# Power.net
KiCad netlist of a schematic drawn in Altium Designer
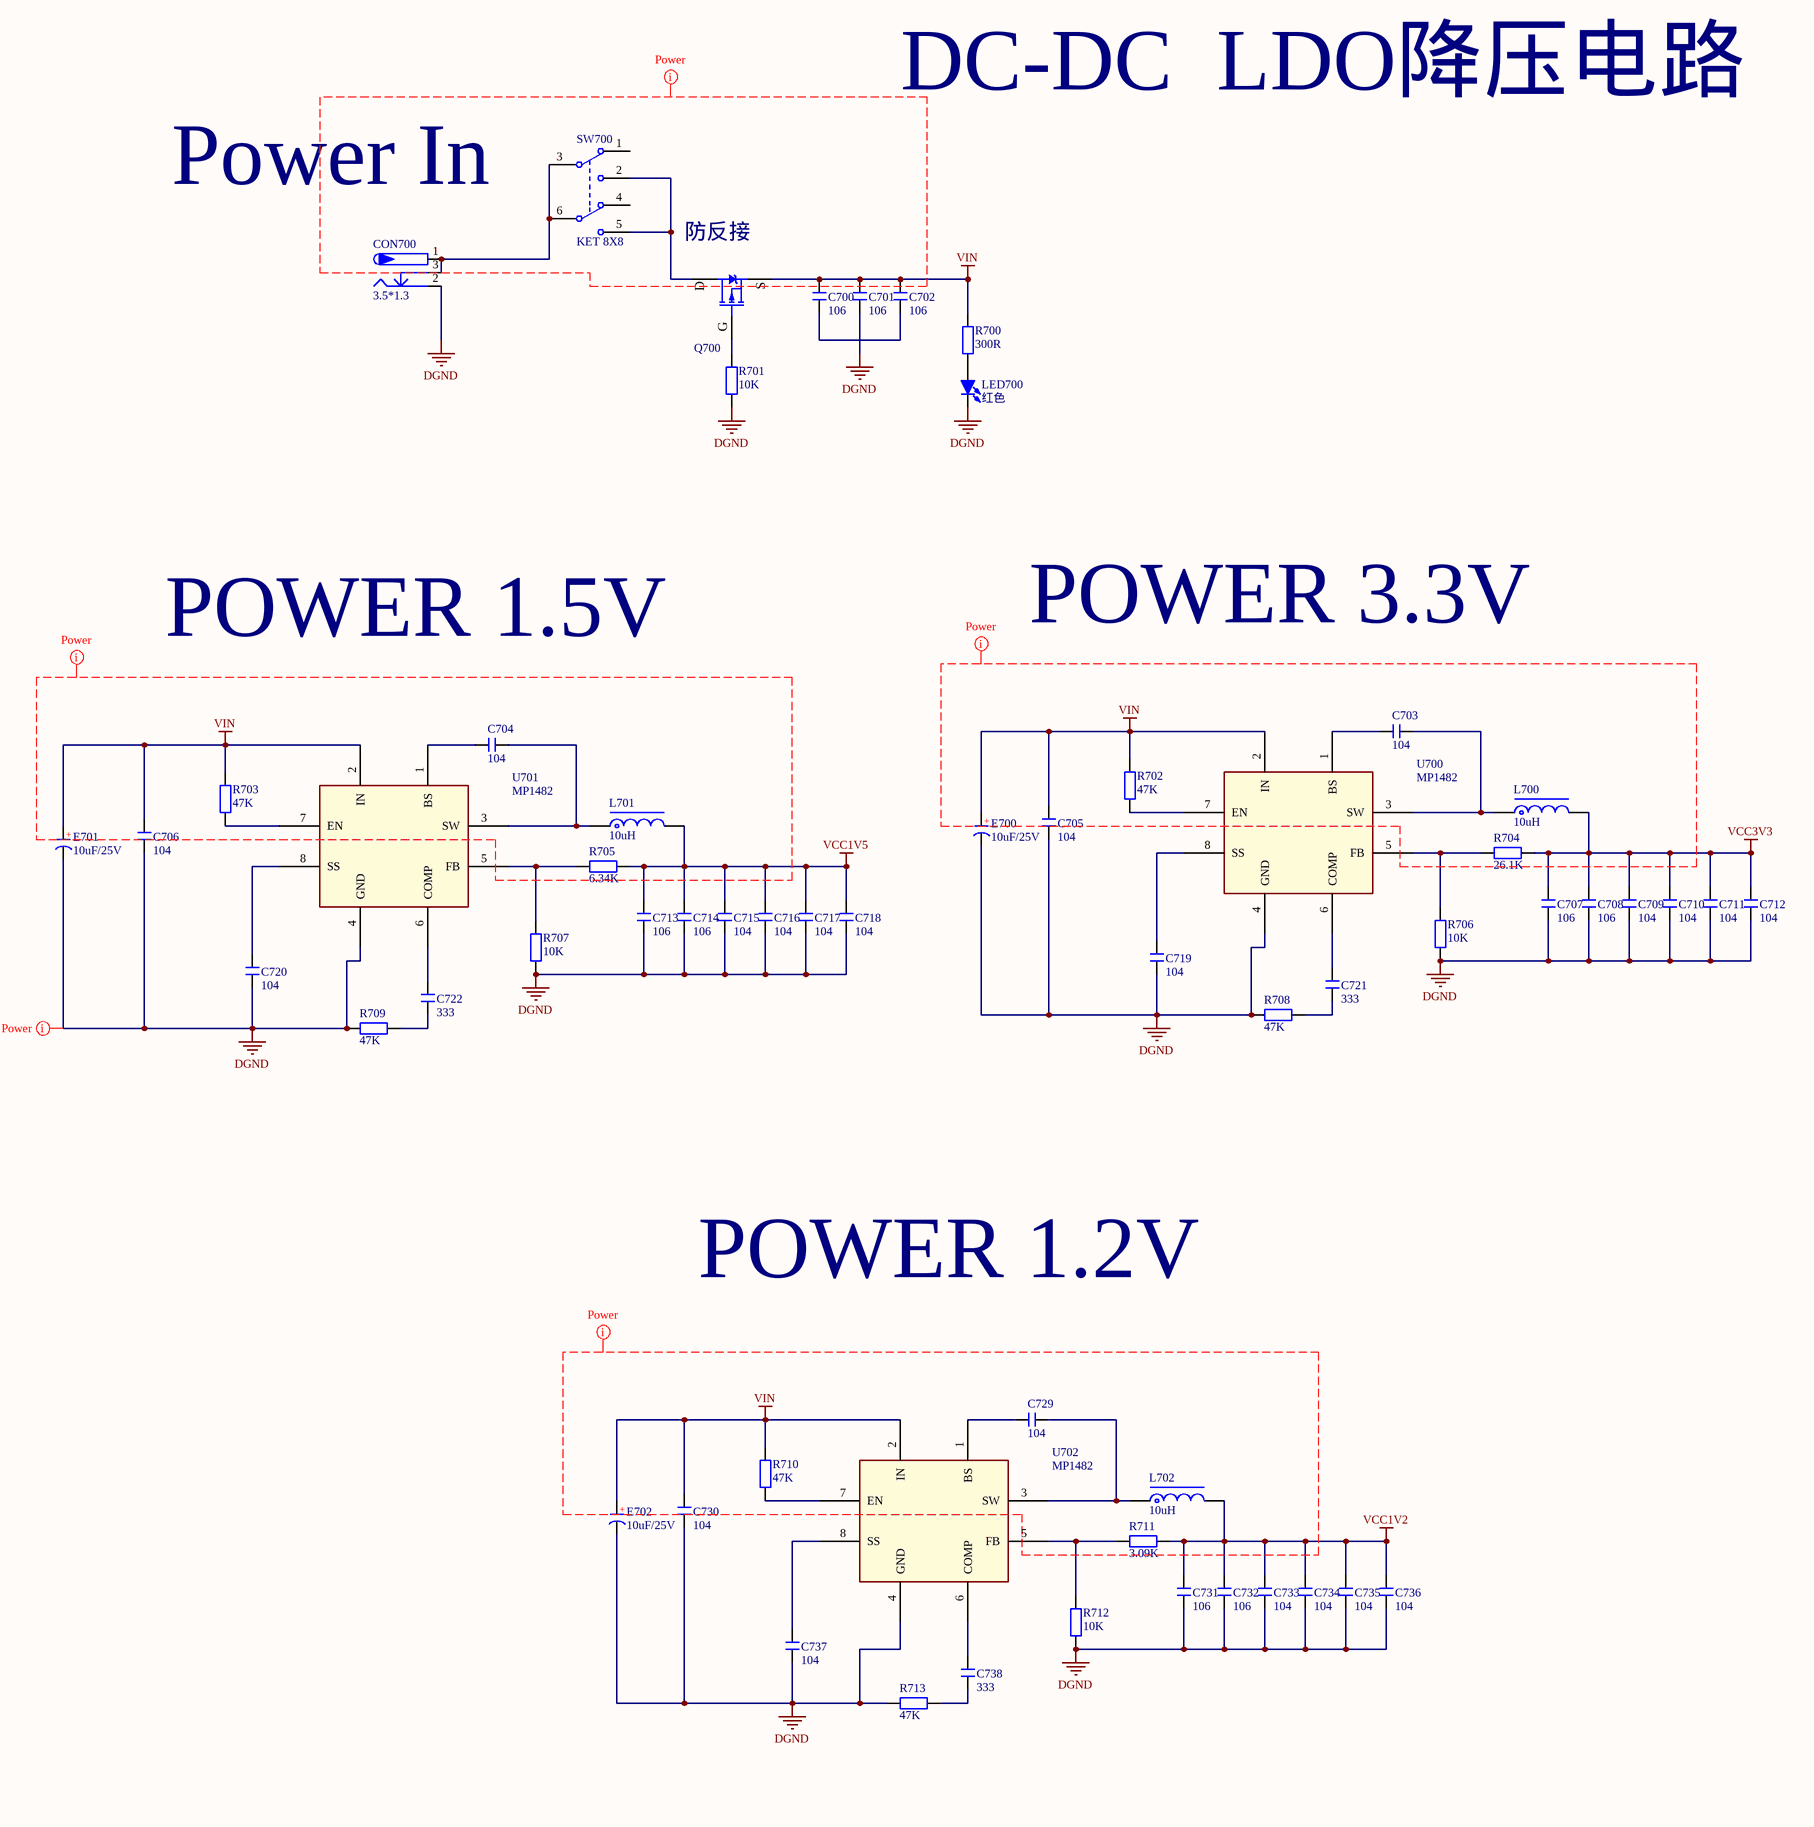
[diagram p0: Power.SchDoc, left]
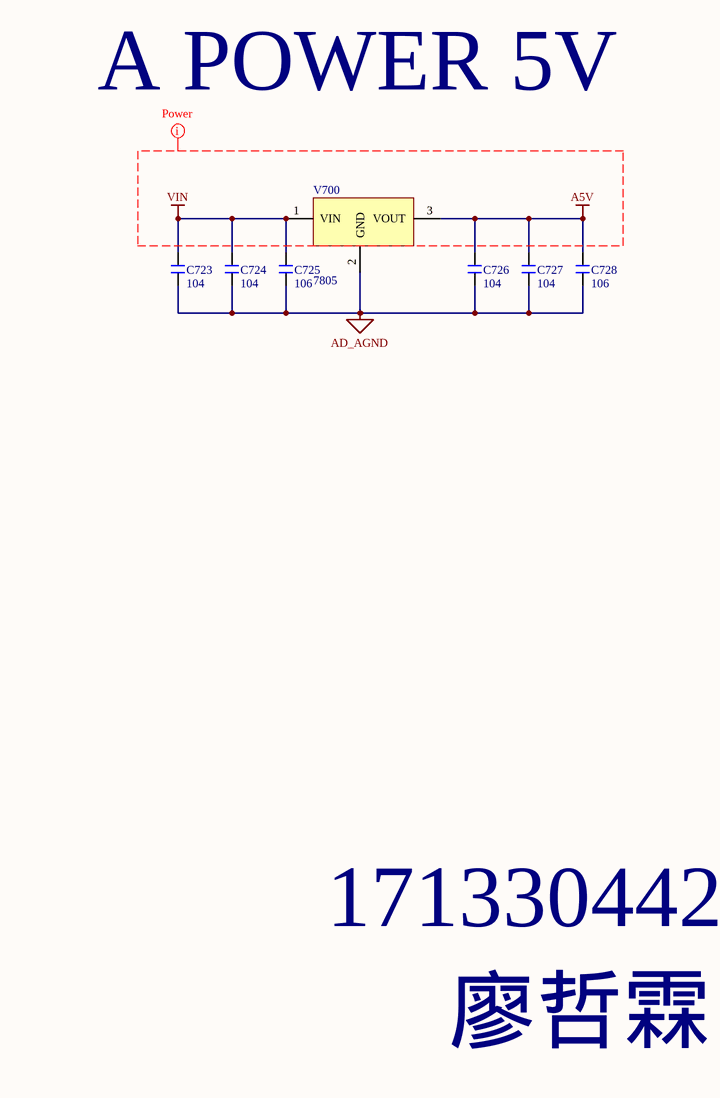
[diagram p1: Power.SchDoc, right]

(export (version "E")
  (design (tool "Eeschema 10.0.6"))
  (components
    (comp (ref "C700")
      (value "106")
      (footprint "C 0402_M")
      (description "无极性贴片电容")
      (fields (field (name "版权归属") "源创客"))
      (libsource (lib "3.1   - 电阻-电容-电感") (part "C"))
    )
    (comp (ref "C701")
      (value "106")
      (footprint "C 0402_M")
      (description "无极性贴片电容")
      (fields (field (name "版权归属") "源创客"))
      (libsource (lib "3.1   - 电阻-电容-电感") (part "C"))
    )
    (comp (ref "C702")
      (value "106")
      (footprint "C 0402_M")
      (description "无极性贴片电容")
      (fields (field (name "版权归属") "源创客"))
      (libsource (lib "3.1   - 电阻-电容-电感") (part "C"))
    )
    (comp (ref "C703")
      (value "104")
      (footprint "C 0402_M")
      (description "无极性贴片电容")
      (fields (field (name "版权归属") "源创客"))
      (libsource (lib "3.1   - 电阻-电容-电感") (part "C"))
    )
    (comp (ref "C704")
      (value "104")
      (footprint "C 0402_M")
      (description "无极性贴片电容")
      (fields (field (name "版权归属") "源创客"))
      (libsource (lib "3.1   - 电阻-电容-电感") (part "C"))
    )
    (comp (ref "C705")
      (value "104")
      (footprint "C 0402_M")
      (description "无极性贴片电容")
      (fields (field (name "版权归属") "源创客"))
      (libsource (lib "3.1   - 电阻-电容-电感") (part "C"))
    )
    (comp (ref "C706")
      (value "104")
      (footprint "C 0402_M")
      (description "无极性贴片电容")
      (fields (field (name "版权归属") "源创客"))
      (libsource (lib "3.1   - 电阻-电容-电感") (part "C"))
    )
    (comp (ref "C707")
      (value "106")
      (footprint "C 0402_M")
      (description "无极性贴片电容")
      (fields (field (name "版权归属") "源创客"))
      (libsource (lib "3.1   - 电阻-电容-电感") (part "C"))
    )
    (comp (ref "C708")
      (value "106")
      (footprint "C 0402_M")
      (description "无极性贴片电容")
      (fields (field (name "版权归属") "源创客"))
      (libsource (lib "3.1   - 电阻-电容-电感") (part "C"))
    )
    (comp (ref "C709")
      (value "104")
      (footprint "C 0402_M")
      (description "无极性贴片电容")
      (fields (field (name "版权归属") "源创客"))
      (libsource (lib "3.1   - 电阻-电容-电感") (part "C"))
    )
    (comp (ref "C710")
      (value "104")
      (footprint "C 0402_M")
      (description "无极性贴片电容")
      (fields (field (name "版权归属") "源创客"))
      (libsource (lib "3.1   - 电阻-电容-电感") (part "C"))
    )
    (comp (ref "C711")
      (value "104")
      (footprint "C 0402_M")
      (description "无极性贴片电容")
      (fields (field (name "版权归属") "源创客"))
      (libsource (lib "3.1   - 电阻-电容-电感") (part "C"))
    )
    (comp (ref "C712")
      (value "104")
      (footprint "C 0402_M")
      (description "无极性贴片电容")
      (fields (field (name "版权归属") "源创客"))
      (libsource (lib "3.1   - 电阻-电容-电感") (part "C"))
    )
    (comp (ref "C713")
      (value "106")
      (footprint "C 0402_M")
      (description "无极性贴片电容")
      (fields (field (name "版权归属") "源创客"))
      (libsource (lib "3.1   - 电阻-电容-电感") (part "C"))
    )
    (comp (ref "C714")
      (value "106")
      (footprint "C 0402_M")
      (description "无极性贴片电容")
      (fields (field (name "版权归属") "源创客"))
      (libsource (lib "3.1   - 电阻-电容-电感") (part "C"))
    )
    (comp (ref "C715")
      (value "104")
      (footprint "C 0402_M")
      (description "无极性贴片电容")
      (fields (field (name "版权归属") "源创客"))
      (libsource (lib "3.1   - 电阻-电容-电感") (part "C"))
    )
    (comp (ref "C716")
      (value "104")
      (footprint "C 0402_M")
      (description "无极性贴片电容")
      (fields (field (name "版权归属") "源创客"))
      (libsource (lib "3.1   - 电阻-电容-电感") (part "C"))
    )
    (comp (ref "C717")
      (value "104")
      (footprint "C 0402_M")
      (description "无极性贴片电容")
      (fields (field (name "版权归属") "源创客"))
      (libsource (lib "3.1   - 电阻-电容-电感") (part "C"))
    )
    (comp (ref "C718")
      (value "104")
      (footprint "C 0402_M")
      (description "无极性贴片电容")
      (fields (field (name "版权归属") "源创客"))
      (libsource (lib "3.1   - 电阻-电容-电感") (part "C"))
    )
    (comp (ref "C719")
      (value "104")
      (footprint "C 0402_M")
      (description "无极性贴片电容")
      (fields (field (name "版权归属") "源创客"))
      (libsource (lib "3.1   - 电阻-电容-电感") (part "C"))
    )
    (comp (ref "C720")
      (value "104")
      (footprint "C 0402_M")
      (description "无极性贴片电容")
      (fields (field (name "版权归属") "源创客"))
      (libsource (lib "3.1   - 电阻-电容-电感") (part "C"))
    )
    (comp (ref "C721")
      (value "333")
      (footprint "C 0402_M")
      (description "无极性贴片电容")
      (fields (field (name "版权归属") "源创客"))
      (libsource (lib "3.1   - 电阻-电容-电感") (part "C"))
    )
    (comp (ref "C722")
      (value "333")
      (footprint "C 0402_M")
      (description "无极性贴片电容")
      (fields (field (name "版权归属") "源创客"))
      (libsource (lib "3.1   - 电阻-电容-电感") (part "C"))
    )
    (comp (ref "C723")
      (value "104")
      (footprint "C 0402_M")
      (description "无极性贴片电容")
      (fields (field (name "版权归属") "源创客"))
      (libsource (lib "3.1   - 电阻-电容-电感") (part "C"))
    )
    (comp (ref "C724")
      (value "104")
      (footprint "C 0402_M")
      (description "无极性贴片电容")
      (fields (field (name "版权归属") "源创客"))
      (libsource (lib "3.1   - 电阻-电容-电感") (part "C"))
    )
    (comp (ref "C725")
      (value "106")
      (footprint "C 0402_M")
      (description "无极性贴片电容")
      (fields (field (name "版权归属") "源创客"))
      (libsource (lib "3.1   - 电阻-电容-电感") (part "C"))
    )
    (comp (ref "C726")
      (value "104")
      (footprint "C 0402_M")
      (description "无极性贴片电容")
      (fields (field (name "版权归属") "源创客"))
      (libsource (lib "3.1   - 电阻-电容-电感") (part "C"))
    )
    (comp (ref "C727")
      (value "104")
      (footprint "C 0402_M")
      (description "无极性贴片电容")
      (fields (field (name "版权归属") "源创客"))
      (libsource (lib "3.1   - 电阻-电容-电感") (part "C"))
    )
    (comp (ref "C728")
      (value "106")
      (footprint "C 0402_M")
      (description "无极性贴片电容")
      (fields (field (name "版权归属") "源创客"))
      (libsource (lib "3.1   - 电阻-电容-电感") (part "C"))
    )
    (comp (ref "C729")
      (value "104")
      (footprint "C 0402_M")
      (description "无极性贴片电容")
      (fields (field (name "版权归属") "源创客"))
      (libsource (lib "3.1   - 电阻-电容-电感") (part "C"))
    )
    (comp (ref "C730")
      (value "104")
      (footprint "C 0402_M")
      (description "无极性贴片电容")
      (fields (field (name "版权归属") "源创客"))
      (libsource (lib "3.1   - 电阻-电容-电感") (part "C"))
    )
    (comp (ref "C731")
      (value "106")
      (footprint "C 0402_M")
      (description "无极性贴片电容")
      (fields (field (name "版权归属") "源创客"))
      (libsource (lib "3.1   - 电阻-电容-电感") (part "C"))
    )
    (comp (ref "C732")
      (value "106")
      (footprint "C 0402_M")
      (description "无极性贴片电容")
      (fields (field (name "版权归属") "源创客"))
      (libsource (lib "3.1   - 电阻-电容-电感") (part "C"))
    )
    (comp (ref "C733")
      (value "104")
      (footprint "C 0402_M")
      (description "无极性贴片电容")
      (fields (field (name "版权归属") "源创客"))
      (libsource (lib "3.1   - 电阻-电容-电感") (part "C"))
    )
    (comp (ref "C734")
      (value "104")
      (footprint "C 0402_M")
      (description "无极性贴片电容")
      (fields (field (name "版权归属") "源创客"))
      (libsource (lib "3.1   - 电阻-电容-电感") (part "C"))
    )
    (comp (ref "C735")
      (value "104")
      (footprint "C 0402_M")
      (description "无极性贴片电容")
      (fields (field (name "版权归属") "源创客"))
      (libsource (lib "3.1   - 电阻-电容-电感") (part "C"))
    )
    (comp (ref "C736")
      (value "104")
      (footprint "C 0402_M")
      (description "无极性贴片电容")
      (fields (field (name "版权归属") "源创客"))
      (libsource (lib "3.1   - 电阻-电容-电感") (part "C"))
    )
    (comp (ref "C737")
      (value "104")
      (footprint "C 0402_M")
      (description "无极性贴片电容")
      (fields (field (name "版权归属") "源创客"))
      (libsource (lib "3.1   - 电阻-电容-电感") (part "C"))
    )
    (comp (ref "C738")
      (value "333")
      (footprint "C 0402_M")
      (description "无极性贴片电容")
      (fields (field (name "版权归属") "源创客"))
      (libsource (lib "3.1   - 电阻-电容-电感") (part "C"))
    )
    (comp (ref "CON700")
      (value "3.5*1.3")
      (footprint "DC-005")
      (description "低压电源接口")
      (fields (field (name "版权归属") "源创客"))
      (libsource (lib "4.1   - 接口类") (part "P-DC"))
    )
    (comp (ref "E700")
      (value "10uF/25V")
      (footprint "CS 2.5*6.3*11 - C")
      (description "直插固态电容")
      (fields (field (name "版权归属") "源创客"))
      (libsource (lib "3.1   - 电阻-电容-电感") (part "C-CS"))
    )
    (comp (ref "E701")
      (value "10uF/25V")
      (footprint "CS 2.5*6.3*11 - C")
      (description "直插固态电容")
      (fields (field (name "版权归属") "源创客"))
      (libsource (lib "3.1   - 电阻-电容-电感") (part "C-CS"))
    )
    (comp (ref "E702")
      (value "10uF/25V")
      (footprint "CS 2.5*6.3*11 - C")
      (description "直插固态电容")
      (fields (field (name "版权归属") "源创客"))
      (libsource (lib "3.1   - 电阻-电容-电感") (part "C-CS"))
    )
    (comp (ref "L700")
      (value "10uH")
      (footprint "CD43")
      (description "贴片功率电感")
      (fields (field (name "版权归属") "源创客"))
      (libsource (lib "3.1   - 电阻-电容-电感") (part "L-CD"))
    )
    (comp (ref "L701")
      (value "10uH")
      (footprint "CD43")
      (description "贴片功率电感")
      (fields (field (name "版权归属") "源创客"))
      (libsource (lib "3.1   - 电阻-电容-电感") (part "L-CD"))
    )
    (comp (ref "L702")
      (value "10uH")
      (footprint "CD43")
      (description "贴片功率电感")
      (fields (field (name "版权归属") "源创客"))
      (libsource (lib "3.1   - 电阻-电容-电感") (part "L-CD"))
    )
    (comp (ref "LED700")
      (value "红色")
      (footprint "LED 0603W")
      (description "贴片LED")
      (fields (field (name "版权归属") "源创客"))
      (libsource (lib "9.1   - LED") (part "LED-SMD"))
    )
    (comp (ref "Q700")
      (value "D15P05")
      (footprint "TO252")
      (description "P沟道场效应管")
      (fields (field (name "版权归属") "源创客"))
      (libsource (lib "6.1   - 场效应管-可控硅") (part "D15P05"))
    )
    (comp (ref "R700")
      (value "300R")
      (footprint "R 0402_M")
      (description "贴片电阻")
      (fields (field (name "版权归属") "源创客"))
      (libsource (lib "3.1   - 电阻-电容-电感") (part "R"))
    )
    (comp (ref "R701")
      (value "10K")
      (footprint "R 0402_M")
      (description "贴片电阻")
      (fields (field (name "版权归属") "源创客"))
      (libsource (lib "3.1   - 电阻-电容-电感") (part "R"))
    )
    (comp (ref "R702")
      (value "47K")
      (footprint "R 0402_M")
      (description "贴片电阻")
      (fields (field (name "版权归属") "源创客"))
      (libsource (lib "3.1   - 电阻-电容-电感") (part "R"))
    )
    (comp (ref "R703")
      (value "47K")
      (footprint "R 0402_M")
      (description "贴片电阻")
      (fields (field (name "版权归属") "源创客"))
      (libsource (lib "3.1   - 电阻-电容-电感") (part "R"))
    )
    (comp (ref "R704")
      (value "26.1K")
      (footprint "R 0402_M")
      (description "贴片电阻")
      (fields (field (name "版权归属") "源创客"))
      (libsource (lib "3.1   - 电阻-电容-电感") (part "R"))
    )
    (comp (ref "R705")
      (value "6.34K")
      (footprint "R 0402_M")
      (description "贴片电阻")
      (fields (field (name "版权归属") "源创客"))
      (libsource (lib "3.1   - 电阻-电容-电感") (part "R"))
    )
    (comp (ref "R706")
      (value "10K")
      (footprint "R 0402_M")
      (description "贴片电阻")
      (fields (field (name "版权归属") "源创客"))
      (libsource (lib "3.1   - 电阻-电容-电感") (part "R"))
    )
    (comp (ref "R707")
      (value "10K")
      (footprint "R 0402_M")
      (description "贴片电阻")
      (fields (field (name "版权归属") "源创客"))
      (libsource (lib "3.1   - 电阻-电容-电感") (part "R"))
    )
    (comp (ref "R708")
      (value "47K")
      (footprint "R 0402_M")
      (description "贴片电阻")
      (fields (field (name "版权归属") "源创客"))
      (libsource (lib "3.1   - 电阻-电容-电感") (part "R"))
    )
    (comp (ref "R709")
      (value "47K")
      (footprint "R 0402_M")
      (description "贴片电阻")
      (fields (field (name "版权归属") "源创客"))
      (libsource (lib "3.1   - 电阻-电容-电感") (part "R"))
    )
    (comp (ref "R710")
      (value "47K")
      (footprint "R 0402_M")
      (description "贴片电阻")
      (fields (field (name "版权归属") "源创客"))
      (libsource (lib "3.1   - 电阻-电容-电感") (part "R"))
    )
    (comp (ref "R711")
      (value "3.09K")
      (footprint "R 0402_M")
      (description "贴片电阻")
      (fields (field (name "版权归属") "源创客"))
      (libsource (lib "3.1   - 电阻-电容-电感") (part "R"))
    )
    (comp (ref "R712")
      (value "10K")
      (footprint "R 0402_M")
      (description "贴片电阻")
      (fields (field (name "版权归属") "源创客"))
      (libsource (lib "3.1   - 电阻-电容-电感") (part "R"))
    )
    (comp (ref "R713")
      (value "47K")
      (footprint "R 0402_M")
      (description "贴片电阻")
      (fields (field (name "版权归属") "源创客"))
      (libsource (lib "3.1   - 电阻-电容-电感") (part "R"))
    )
    (comp (ref "SW700")
      (value "KET 8X8")
      (footprint "KFT DIP-8X8")
      (description "8*8自锁开关")
      (fields (field (name "版权归属") "源创客"))
      (libsource (lib "5.1   - 按键-开关") (part "KET 8X8"))
    )
    (comp (ref "U700")
      (value "MP1482")
      (footprint "SOP8_M")
      (libsource (lib "altium-import") (part "root_0_MP1482_"))
    )
    (comp (ref "U701")
      (value "MP1482")
      (footprint "SOP8_M")
      (libsource (lib "altium-import") (part "root_0_MP1482_"))
    )
    (comp (ref "U702")
      (value "MP1482")
      (footprint "SOP8_M")
      (libsource (lib "altium-import") (part "root_0_MP1482_"))
    )
    (comp (ref "V700")
      (value "7805")
      (footprint "TO252")
      (description "线性稳压芯片")
      (fields (field (name "版权归属") "源创客"))
      (libsource (lib "1.3   - 电源类芯片") (part "78xx"))
    )
  )
  (nets
    (net (code "1") (name "A5V") (class "Default")
      (node (ref "C726") (pin "2") (pinfunction "2_2") (pintype "passive"))
      (node (ref "C727") (pin "2") (pinfunction "2_2") (pintype "passive"))
      (node (ref "C728") (pin "2") (pinfunction "2_2") (pintype "passive"))
      (node (ref "V700") (pin "3") (pinfunction "VOUT_3") (pintype "passive"))
    )
    (net (code "2") (name "AD_AGND") (class "Default")
      (node (ref "C723") (pin "1") (pinfunction "1_1") (pintype "passive"))
      (node (ref "C724") (pin "1") (pinfunction "1_1") (pintype "passive"))
      (node (ref "C725") (pin "1") (pinfunction "1_1") (pintype "passive"))
      (node (ref "C726") (pin "1") (pinfunction "1_1") (pintype "passive"))
      (node (ref "C727") (pin "1") (pinfunction "1_1") (pintype "passive"))
      (node (ref "C728") (pin "1") (pinfunction "1_1") (pintype "passive"))
      (node (ref "V700") (pin "2") (pinfunction "GND_2") (pintype "passive"))
    )
    (net (code "3") (name "DGND") (class "Default")
      (node (ref "C701") (pin "1") (pinfunction "1_1") (pintype "passive"))
      (node (ref "C705") (pin "1") (pinfunction "1_1") (pintype "passive"))
      (node (ref "C706") (pin "1") (pinfunction "1_1") (pintype "passive"))
      (node (ref "C707") (pin "1") (pinfunction "1_1") (pintype "passive"))
      (node (ref "C708") (pin "1") (pinfunction "1_1") (pintype "passive"))
      (node (ref "C709") (pin "1") (pinfunction "1_1") (pintype "passive"))
      (node (ref "C710") (pin "1") (pinfunction "1_1") (pintype "passive"))
      (node (ref "C711") (pin "1") (pinfunction "1_1") (pintype "passive"))
      (node (ref "C712") (pin "1") (pinfunction "1_1") (pintype "passive"))
      (node (ref "C713") (pin "1") (pinfunction "1_1") (pintype "passive"))
      (node (ref "C714") (pin "1") (pinfunction "1_1") (pintype "passive"))
      (node (ref "C715") (pin "1") (pinfunction "1_1") (pintype "passive"))
      (node (ref "C716") (pin "1") (pinfunction "1_1") (pintype "passive"))
      (node (ref "C717") (pin "1") (pinfunction "1_1") (pintype "passive"))
      (node (ref "C718") (pin "1") (pinfunction "1_1") (pintype "passive"))
      (node (ref "C719") (pin "1") (pinfunction "1_1") (pintype "passive"))
      (node (ref "C720") (pin "1") (pinfunction "1_1") (pintype "passive"))
      (node (ref "C730") (pin "1") (pinfunction "1_1") (pintype "passive"))
      (node (ref "C731") (pin "1") (pinfunction "1_1") (pintype "passive"))
      (node (ref "C732") (pin "1") (pinfunction "1_1") (pintype "passive"))
      (node (ref "C733") (pin "1") (pinfunction "1_1") (pintype "passive"))
      (node (ref "C734") (pin "1") (pinfunction "1_1") (pintype "passive"))
      (node (ref "C735") (pin "1") (pinfunction "1_1") (pintype "passive"))
      (node (ref "C736") (pin "1") (pinfunction "1_1") (pintype "passive"))
      (node (ref "C737") (pin "1") (pinfunction "1_1") (pintype "passive"))
      (node (ref "CON700") (pin "2") (pintype "power_in"))
      (node (ref "E700") (pin "2") (pinfunction "K_2") (pintype "passive"))
      (node (ref "E701") (pin "2") (pinfunction "K_2") (pintype "passive"))
      (node (ref "E702") (pin "2") (pinfunction "K_2") (pintype "passive"))
      (node (ref "LED700") (pin "2") (pinfunction "K_2") (pintype "passive"))
      (node (ref "R701") (pin "2") (pinfunction "2_2") (pintype "passive"))
      (node (ref "R706") (pin "2") (pinfunction "2_2") (pintype "passive"))
      (node (ref "R707") (pin "2") (pinfunction "2_2") (pintype "passive"))
      (node (ref "R708") (pin "2") (pinfunction "2_2") (pintype "passive"))
      (node (ref "R709") (pin "2") (pinfunction "2_2") (pintype "passive"))
      (node (ref "R712") (pin "2") (pinfunction "2_2") (pintype "passive"))
      (node (ref "R713") (pin "2") (pinfunction "2_2") (pintype "passive"))
      (node (ref "U700") (pin "4") (pinfunction "GND_4") (pintype "passive"))
      (node (ref "U701") (pin "4") (pinfunction "GND_4") (pintype "passive"))
      (node (ref "U702") (pin "4") (pinfunction "GND_4") (pintype "passive"))
    )
    (net (code "4") (name "Net-(C700-Pad1)") (class "Default")
      (node (ref "C700") (pin "1") (pinfunction "1_1") (pintype "passive"))
      (node (ref "C702") (pin "1") (pinfunction "1_1") (pintype "passive"))
    )
    (net (code "5") (name "Net-(C721-Pad1)") (class "Default")
      (node (ref "C721") (pin "1") (pinfunction "1_1") (pintype "passive"))
      (node (ref "R708") (pin "1") (pinfunction "1_1") (pintype "passive"))
    )
    (net (code "6") (name "Net-(C722-Pad1)") (class "Default")
      (node (ref "C722") (pin "1") (pinfunction "1_1") (pintype "passive"))
      (node (ref "R709") (pin "1") (pinfunction "1_1") (pintype "passive"))
    )
    (net (code "7") (name "Net-(C738-Pad1)") (class "Default")
      (node (ref "C738") (pin "1") (pinfunction "1_1") (pintype "passive"))
      (node (ref "R713") (pin "1") (pinfunction "1_1") (pintype "passive"))
    )
    (net (code "8") (name "Net-(LED700-A)") (class "Default")
      (node (ref "LED700") (pin "1") (pinfunction "A_1") (pintype "passive"))
      (node (ref "R700") (pin "2") (pinfunction "2_2") (pintype "passive"))
    )
    (net (code "9") (name "Net-(Q700-D)") (class "Default")
      (node (ref "Q700") (pin "2") (pinfunction "D_2") (pintype "passive"))
      (node (ref "SW700") (pin "2") (pinfunction "COM2_2") (pintype "passive"))
      (node (ref "SW700") (pin "5") (pinfunction "COM2_5") (pintype "passive"))
    )
    (net (code "10") (name "Net-(Q700-G)") (class "Default")
      (node (ref "Q700") (pin "1") (pinfunction "G_1") (pintype "passive"))
      (node (ref "R701") (pin "1") (pinfunction "1_1") (pintype "passive"))
    )
    (net (code "11") (name "Net-(SW700-NC2)") (class "Default")
      (node (ref "CON700") (pin "1") (pintype "power_in"))
      (node (ref "CON700") (pin "3") (pintype "power_in"))
      (node (ref "SW700") (pin "3") (pinfunction "NO1_3") (pintype "passive"))
      (node (ref "SW700") (pin "6") (pinfunction "NC2_6") (pintype "passive"))
    )
    (net (code "12") (name "Net-(U700-BS)") (class "Default")
      (node (ref "C703") (pin "2") (pinfunction "2_2") (pintype "passive"))
      (node (ref "U700") (pin "1") (pinfunction "BS_1") (pintype "passive"))
    )
    (net (code "13") (name "Net-(U700-COMP)") (class "Default")
      (node (ref "C721") (pin "2") (pinfunction "2_2") (pintype "passive"))
      (node (ref "U700") (pin "6") (pinfunction "COMP_6") (pintype "passive"))
    )
    (net (code "14") (name "Net-(U700-EN)") (class "Default")
      (node (ref "R702") (pin "1") (pinfunction "1_1") (pintype "passive"))
      (node (ref "U700") (pin "7") (pinfunction "EN_7") (pintype "passive"))
    )
    (net (code "15") (name "Net-(U700-FB)") (class "Default")
      (node (ref "R704") (pin "2") (pinfunction "2_2") (pintype "passive"))
      (node (ref "R706") (pin "1") (pinfunction "1_1") (pintype "passive"))
      (node (ref "U700") (pin "5") (pinfunction "FB_5") (pintype "passive"))
    )
    (net (code "16") (name "Net-(U700-SS)") (class "Default")
      (node (ref "C719") (pin "2") (pinfunction "2_2") (pintype "passive"))
      (node (ref "U700") (pin "8") (pinfunction "SS_8") (pintype "passive"))
    )
    (net (code "17") (name "Net-(U700-SW)") (class "Default")
      (node (ref "C703") (pin "1") (pinfunction "1_1") (pintype "passive"))
      (node (ref "L700") (pin "1") (pinfunction "1_1") (pintype "passive"))
      (node (ref "U700") (pin "3") (pinfunction "SW_3") (pintype "passive"))
    )
    (net (code "18") (name "Net-(U701-BS)") (class "Default")
      (node (ref "C704") (pin "2") (pinfunction "2_2") (pintype "passive"))
      (node (ref "U701") (pin "1") (pinfunction "BS_1") (pintype "passive"))
    )
    (net (code "19") (name "Net-(U701-COMP)") (class "Default")
      (node (ref "C722") (pin "2") (pinfunction "2_2") (pintype "passive"))
      (node (ref "U701") (pin "6") (pinfunction "COMP_6") (pintype "passive"))
    )
    (net (code "20") (name "Net-(U701-EN)") (class "Default")
      (node (ref "R703") (pin "1") (pinfunction "1_1") (pintype "passive"))
      (node (ref "U701") (pin "7") (pinfunction "EN_7") (pintype "passive"))
    )
    (net (code "21") (name "Net-(U701-FB)") (class "Default")
      (node (ref "R705") (pin "2") (pinfunction "2_2") (pintype "passive"))
      (node (ref "R707") (pin "1") (pinfunction "1_1") (pintype "passive"))
      (node (ref "U701") (pin "5") (pinfunction "FB_5") (pintype "passive"))
    )
    (net (code "22") (name "Net-(U701-SS)") (class "Default")
      (node (ref "C720") (pin "2") (pinfunction "2_2") (pintype "passive"))
      (node (ref "U701") (pin "8") (pinfunction "SS_8") (pintype "passive"))
    )
    (net (code "23") (name "Net-(U701-SW)") (class "Default")
      (node (ref "C704") (pin "1") (pinfunction "1_1") (pintype "passive"))
      (node (ref "L701") (pin "1") (pinfunction "1_1") (pintype "passive"))
      (node (ref "U701") (pin "3") (pinfunction "SW_3") (pintype "passive"))
    )
    (net (code "24") (name "Net-(U702-BS)") (class "Default")
      (node (ref "C729") (pin "2") (pinfunction "2_2") (pintype "passive"))
      (node (ref "U702") (pin "1") (pinfunction "BS_1") (pintype "passive"))
    )
    (net (code "25") (name "Net-(U702-COMP)") (class "Default")
      (node (ref "C738") (pin "2") (pinfunction "2_2") (pintype "passive"))
      (node (ref "U702") (pin "6") (pinfunction "COMP_6") (pintype "passive"))
    )
    (net (code "26") (name "Net-(U702-EN)") (class "Default")
      (node (ref "R710") (pin "1") (pinfunction "1_1") (pintype "passive"))
      (node (ref "U702") (pin "7") (pinfunction "EN_7") (pintype "passive"))
    )
    (net (code "27") (name "Net-(U702-FB)") (class "Default")
      (node (ref "R711") (pin "2") (pinfunction "2_2") (pintype "passive"))
      (node (ref "R712") (pin "1") (pinfunction "1_1") (pintype "passive"))
      (node (ref "U702") (pin "5") (pinfunction "FB_5") (pintype "passive"))
    )
    (net (code "28") (name "Net-(U702-SS)") (class "Default")
      (node (ref "C737") (pin "2") (pinfunction "2_2") (pintype "passive"))
      (node (ref "U702") (pin "8") (pinfunction "SS_8") (pintype "passive"))
    )
    (net (code "29") (name "Net-(U702-SW)") (class "Default")
      (node (ref "C729") (pin "1") (pinfunction "1_1") (pintype "passive"))
      (node (ref "L702") (pin "1") (pinfunction "1_1") (pintype "passive"))
      (node (ref "U702") (pin "3") (pinfunction "SW_3") (pintype "passive"))
    )
    (net (code "30") (name "VCC1V2") (class "Default")
      (node (ref "C731") (pin "2") (pinfunction "2_2") (pintype "passive"))
      (node (ref "C732") (pin "2") (pinfunction "2_2") (pintype "passive"))
      (node (ref "C733") (pin "2") (pinfunction "2_2") (pintype "passive"))
      (node (ref "C734") (pin "2") (pinfunction "2_2") (pintype "passive"))
      (node (ref "C735") (pin "2") (pinfunction "2_2") (pintype "passive"))
      (node (ref "C736") (pin "2") (pinfunction "2_2") (pintype "passive"))
      (node (ref "L702") (pin "2") (pinfunction "2_2") (pintype "passive"))
      (node (ref "R711") (pin "1") (pinfunction "1_1") (pintype "passive"))
    )
    (net (code "31") (name "VCC1V5") (class "Default")
      (node (ref "C713") (pin "2") (pinfunction "2_2") (pintype "passive"))
      (node (ref "C714") (pin "2") (pinfunction "2_2") (pintype "passive"))
      (node (ref "C715") (pin "2") (pinfunction "2_2") (pintype "passive"))
      (node (ref "C716") (pin "2") (pinfunction "2_2") (pintype "passive"))
      (node (ref "C717") (pin "2") (pinfunction "2_2") (pintype "passive"))
      (node (ref "C718") (pin "2") (pinfunction "2_2") (pintype "passive"))
      (node (ref "L701") (pin "2") (pinfunction "2_2") (pintype "passive"))
      (node (ref "R705") (pin "1") (pinfunction "1_1") (pintype "passive"))
    )
    (net (code "32") (name "VCC3V3") (class "Default")
      (node (ref "C707") (pin "2") (pinfunction "2_2") (pintype "passive"))
      (node (ref "C708") (pin "2") (pinfunction "2_2") (pintype "passive"))
      (node (ref "C709") (pin "2") (pinfunction "2_2") (pintype "passive"))
      (node (ref "C710") (pin "2") (pinfunction "2_2") (pintype "passive"))
      (node (ref "C711") (pin "2") (pinfunction "2_2") (pintype "passive"))
      (node (ref "C712") (pin "2") (pinfunction "2_2") (pintype "passive"))
      (node (ref "L700") (pin "2") (pinfunction "2_2") (pintype "passive"))
      (node (ref "R704") (pin "1") (pinfunction "1_1") (pintype "passive"))
    )
    (net (code "33") (name "VIN") (class "Default")
      (node (ref "C700") (pin "2") (pinfunction "2_2") (pintype "passive"))
      (node (ref "C701") (pin "2") (pinfunction "2_2") (pintype "passive"))
      (node (ref "C702") (pin "2") (pinfunction "2_2") (pintype "passive"))
      (node (ref "C705") (pin "2") (pinfunction "2_2") (pintype "passive"))
      (node (ref "C706") (pin "2") (pinfunction "2_2") (pintype "passive"))
      (node (ref "C723") (pin "2") (pinfunction "2_2") (pintype "passive"))
      (node (ref "C724") (pin "2") (pinfunction "2_2") (pintype "passive"))
      (node (ref "C725") (pin "2") (pinfunction "2_2") (pintype "passive"))
      (node (ref "C730") (pin "2") (pinfunction "2_2") (pintype "passive"))
      (node (ref "E700") (pin "1") (pinfunction "A_1") (pintype "passive"))
      (node (ref "E701") (pin "1") (pinfunction "A_1") (pintype "passive"))
      (node (ref "E702") (pin "1") (pinfunction "A_1") (pintype "passive"))
      (node (ref "Q700") (pin "3") (pinfunction "S_3") (pintype "passive"))
      (node (ref "R700") (pin "1") (pinfunction "1_1") (pintype "passive"))
      (node (ref "R702") (pin "2") (pinfunction "2_2") (pintype "passive"))
      (node (ref "R703") (pin "2") (pinfunction "2_2") (pintype "passive"))
      (node (ref "R710") (pin "2") (pinfunction "2_2") (pintype "passive"))
      (node (ref "U700") (pin "2") (pinfunction "IN_2") (pintype "passive"))
      (node (ref "U701") (pin "2") (pinfunction "IN_2") (pintype "passive"))
      (node (ref "U702") (pin "2") (pinfunction "IN_2") (pintype "passive"))
      (node (ref "V700") (pin "1") (pinfunction "VIN_1") (pintype "passive"))
    )
    (net (code "34") (name "unconnected-(SW700-NC1-Pad1)") (class "Default")
      (node (ref "SW700") (pin "1") (pinfunction "NC1_1") (pintype "passive"))
    )
    (net (code "35") (name "unconnected-(SW700-NO2-Pad4)") (class "Default")
      (node (ref "SW700") (pin "4") (pinfunction "NO2_4") (pintype "passive"))
    )
  )
)
